# PG04_Schematic_Sheet2.net
KiCad netlist of a schematic drawn in Altium Designer
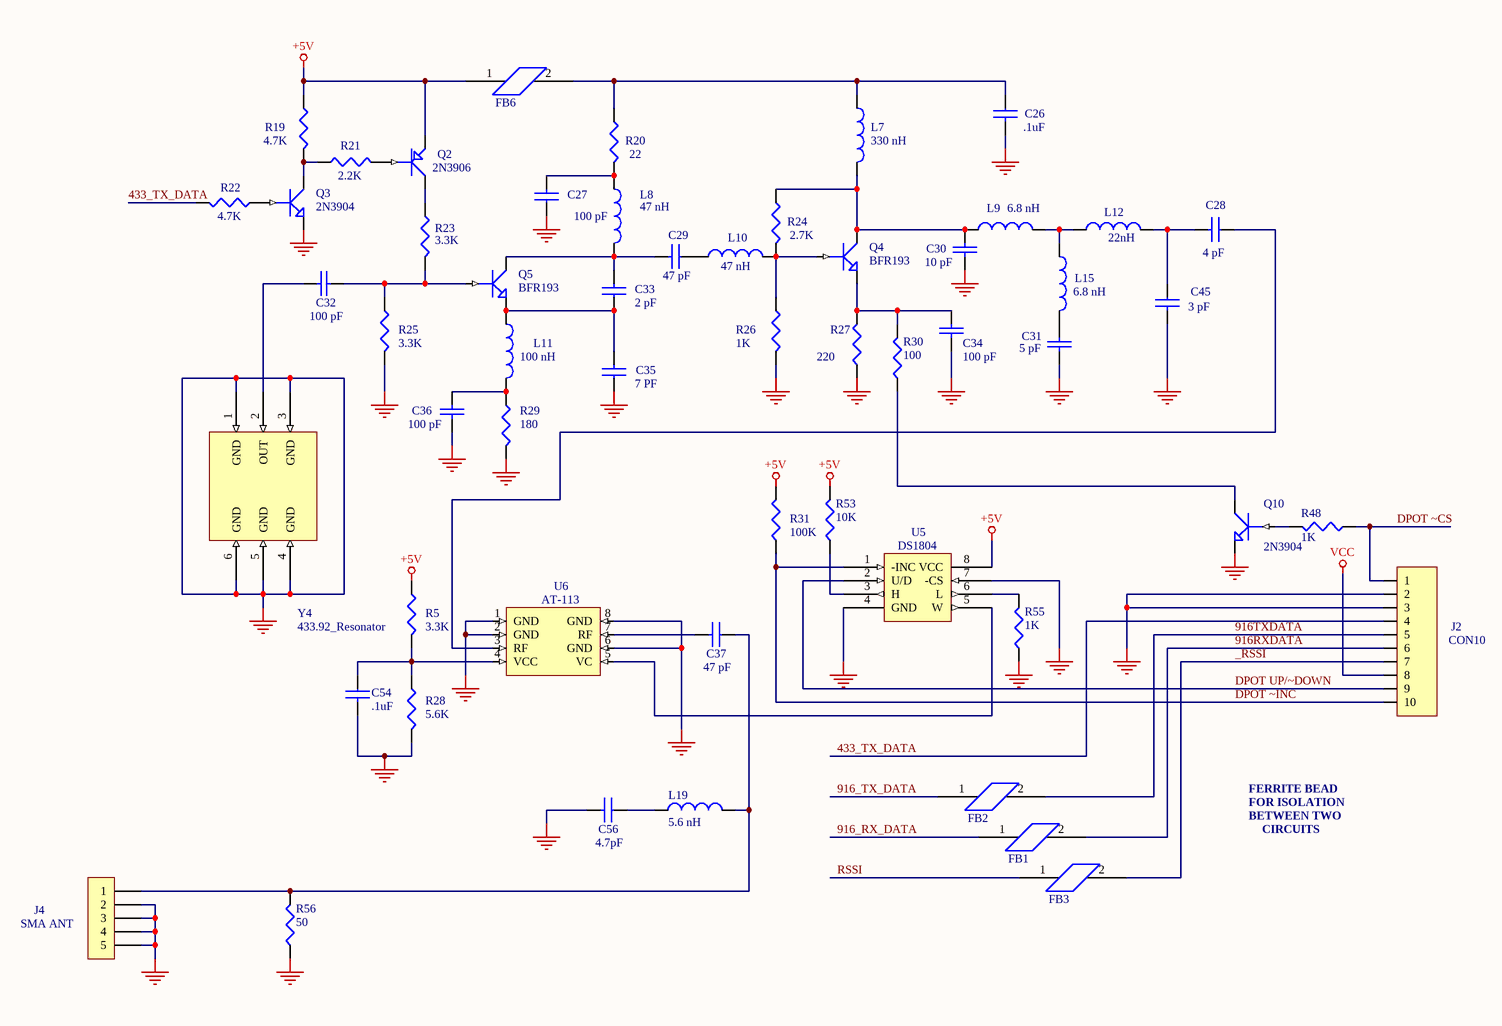
[diagram p0: PG04_Schematic Sheet2.SchDoc]

(export (version "E")
  (design (tool "Eeschema 10.0.6"))
  (components
    (comp (ref "C26") (value ".1uF") (footprint "0603") (libsource (lib "*") (part "CAP_NP")))
    (comp (ref "C27") (value "100 pF") (footprint "0603") (libsource (lib "*") (part "CAP_NP")))
    (comp (ref "C28") (value "4 pF") (footprint "0603") (libsource (lib "*") (part "CAP_NP")))
    (comp (ref "C29") (value "47 pF") (footprint "0603") (libsource (lib "*") (part "CAP_NP")))
    (comp (ref "C30")
      (value "10 pF")
      (footprint "0603")
      (description "Capacitor")
      (libsource (lib "*") (part "CAP"))
    )
    (comp (ref "C31")
      (value "5 pF")
      (footprint "0603")
      (description "Capacitor")
      (libsource (lib "*") (part "CAP"))
    )
    (comp (ref "C32")
      (value "100 pF")
      (footprint "0603")
      (description "Capacitor")
      (libsource (lib "*") (part "CAP"))
    )
    (comp (ref "C33") (value "2 pF") (footprint "0603") (libsource (lib "*") (part "CAP_NP")))
    (comp (ref "C34")
      (value "100 pF")
      (footprint "0603")
      (description "Capacitor")
      (libsource (lib "*") (part "CAP"))
    )
    (comp (ref "C35") (value "7 PF") (footprint "0603") (libsource (lib "*") (part "CAP_NP")))
    (comp (ref "C36")
      (value "100 pF")
      (footprint "0603")
      (description "Capacitor")
      (libsource (lib "*") (part "CAP"))
    )
    (comp (ref "C37") (value "47 pF") (footprint "0603") (libsource (lib "*") (part "CAP_NP")))
    (comp (ref "C45") (value "3 pF") (footprint "0603") (libsource (lib "*") (part "CAP_NP")))
    (comp (ref "C54") (value ".1uF") (footprint "0603") (libsource (lib "*") (part "CAP_NP")))
    (comp (ref "C56") (value "4.7pF") (footprint "0603") (libsource (lib "*") (part "CAP_NP")))
    (comp (ref "FB1") (value "FB") (footprint "0603") (libsource (lib "*") (part "FB_0603")))
    (comp (ref "FB2") (value "FB") (footprint "0603") (libsource (lib "*") (part "FB_0603")))
    (comp (ref "FB3") (value "FB") (footprint "0603") (libsource (lib "*") (part "FB_0603")))
    (comp (ref "FB6") (value "FB") (footprint "0603") (libsource (lib "*") (part "FB_0603")))
    (comp (ref "J2") (value "CON10") (footprint "1X10 HEADER") (libsource (lib "*") (part "CON10")))
    (comp (ref "J4")
      (value "SMA ANT")
      (footprint "50 OHM ANT")
      (description "Connector")
      (libsource (lib "*") (part "CON5"))
    )
    (comp (ref "L7") (value "330 nH") (footprint "0805") (libsource (lib "*") (part "INDUCTOR")))
    (comp (ref "L8") (value "47 nH") (footprint "0603") (libsource (lib "*") (part "INDUCTOR")))
    (comp (ref "L9") (value "6.8 nH") (footprint "0603") (libsource (lib "*") (part "INDUCTOR")))
    (comp (ref "L10") (value "47 nH") (footprint "0603") (libsource (lib "*") (part "INDUCTOR")))
    (comp (ref "L11") (value "100 nH") (footprint "0603") (libsource (lib "*") (part "INDUCTOR")))
    (comp (ref "L12") (value "22nH") (footprint "0603") (libsource (lib "*") (part "INDUCTOR")))
    (comp (ref "L15") (value "6.8 nH") (footprint "0603") (libsource (lib "*") (part "INDUCTOR")))
    (comp (ref "L19") (value "5.6 nH") (footprint "0603") (libsource (lib "*") (part "INDUCTOR")))
    (comp (ref "Q2")
      (value "2N3906")
      (footprint "SOT23 TRANS")
      (description "PNP Transistor")
      (libsource (lib "*") (part "PNP1"))
    )
    (comp (ref "Q3")
      (value "2N3904")
      (footprint "SOT23 TRANS")
      (description "NPN Transistor")
      (libsource (lib "*") (part "NPN1"))
    )
    (comp (ref "Q4")
      (value "BFR193")
      (footprint "SOT23 TRANS")
      (description "NPN Transistor")
      (libsource (lib "*") (part "NPN1"))
    )
    (comp (ref "Q5")
      (value "BFR193")
      (footprint "SOT23 TRANS")
      (description "NPN Transistor")
      (libsource (lib "*") (part "NPN1"))
    )
    (comp (ref "Q10")
      (value "2N3904")
      (footprint "SOT23 TRANS")
      (description "NPN Transistor")
      (libsource (lib "*") (part "NPN1"))
    )
    (comp (ref "R5") (value "3.3K") (footprint "0603") (libsource (lib "*") (part "RESISTOR")))
    (comp (ref "R19") (value "4.7K") (footprint "0603") (libsource (lib "*") (part "RESISTOR")))
    (comp (ref "R20") (value "22") (footprint "0603") (libsource (lib "*") (part "RESISTOR")))
    (comp (ref "R21") (value "2.2K") (footprint "0603") (libsource (lib "*") (part "RESISTOR")))
    (comp (ref "R22") (value "4.7K") (footprint "0603") (libsource (lib "*") (part "RESISTOR")))
    (comp (ref "R23") (value "3.3K") (footprint "0603") (libsource (lib "*") (part "RESISTOR")))
    (comp (ref "R24") (value "2.7K") (footprint "0603") (libsource (lib "*") (part "RESISTOR")))
    (comp (ref "R25") (value "3.3K") (footprint "0603") (libsource (lib "*") (part "RESISTOR")))
    (comp (ref "R26") (value "1K") (footprint "0603") (libsource (lib "*") (part "RESISTOR")))
    (comp (ref "R27") (value "220") (footprint "0603") (libsource (lib "*") (part "RESISTOR")))
    (comp (ref "R28") (value "5.6K") (footprint "0603") (libsource (lib "*") (part "RESISTOR")))
    (comp (ref "R29") (value "180") (footprint "0603") (libsource (lib "*") (part "RESISTOR")))
    (comp (ref "R30") (value "100") (footprint "0603") (libsource (lib "*") (part "RESISTOR")))
    (comp (ref "R31") (value "100K") (footprint "0603") (libsource (lib "*") (part "RESISTOR")))
    (comp (ref "R48") (value "1K") (footprint "0603") (libsource (lib "*") (part "RESISTOR")))
    (comp (ref "R53") (value "10K") (footprint "0603") (libsource (lib "*") (part "RESISTOR")))
    (comp (ref "R55") (value "1K") (footprint "0603") (libsource (lib "*") (part "RESISTOR")))
    (comp (ref "R56") (value "50") (footprint "0603") (libsource (lib "*") (part "RESISTOR")))
    (comp (ref "U5") (value "DS1804") (footprint "SO8 SMALL") (libsource (lib "*") (part "DS1804")))
    (comp (ref "U6") (value "AT-113") (footprint "SO8") (libsource (lib "*") (part "AT-113A")))
    (comp (ref "Y4")
      (value "433.92_Resonator")
      (footprint "RESONATOR2")
      (libsource (lib "*") (part "RESONATOR2"))
    )
  )
  (nets
    (net (code "1") (name "+5V") (class "Default")
      (node (ref "FB6") (pin "1") (pinfunction "2_1") (pintype "passive"))
      (node (ref "Q2") (pin "E") (pinfunction "E_E") (pintype "passive"))
      (node (ref "R19") (pin "1") (pinfunction "1_1") (pintype "passive"))
      (node (ref "R31") (pin "1") (pinfunction "1_1") (pintype "passive"))
      (node (ref "R5") (pin "1") (pinfunction "1_1") (pintype "passive"))
      (node (ref "R53") (pin "2") (pinfunction "2_2") (pintype "passive"))
      (node (ref "U5") (pin "8") (pinfunction "VCC_8") (pintype "power_in"))
    )
    (net (code "2") (name "/433_TX_DATA") (class "Default")
      (node (ref "J2") (pin "4") (pinfunction "4_4") (pintype "passive"))
      (node (ref "R22") (pin "2") (pinfunction "2_2") (pintype "passive"))
    )
    (net (code "3") (name "/916RXDATA") (class "Default")
      (node (ref "FB1") (pin "2") (pinfunction "1_2") (pintype "passive"))
      (node (ref "J2") (pin "6") (pinfunction "6_6") (pintype "passive"))
    )
    (net (code "4") (name "/916TXDATA") (class "Default")
      (node (ref "FB2") (pin "2") (pinfunction "1_2") (pintype "passive"))
      (node (ref "J2") (pin "5") (pinfunction "5_5") (pintype "passive"))
    )
    (net (code "5") (name "/916_RX_DATA") (class "Default")
      (node (ref "FB1") (pin "1") (pinfunction "2_1") (pintype "passive"))
    )
    (net (code "6") (name "/916_TX_DATA") (class "Default")
      (node (ref "FB2") (pin "1") (pinfunction "2_1") (pintype "passive"))
    )
    (net (code "7") (name "/DPOT UP{slash}~DOWN") (class "Default")
      (node (ref "J2") (pin "9") (pinfunction "9_9") (pintype "passive"))
      (node (ref "U5") (pin "2") (pinfunction "U/D_2") (pintype "input"))
    )
    (net (code "8") (name "/DPOT ~CS") (class "Default")
      (node (ref "J2") (pin "1") (pinfunction "1_1") (pintype "passive"))
      (node (ref "R48") (pin "2") (pinfunction "2_2") (pintype "passive"))
    )
    (net (code "9") (name "/DPOT ~INC") (class "Default")
      (node (ref "J2") (pin "10") (pinfunction "10_10") (pintype "passive"))
      (node (ref "R31") (pin "2") (pinfunction "2_2") (pintype "passive"))
      (node (ref "U5") (pin "1") (pinfunction "-INC_1") (pintype "input"))
    )
    (net (code "10") (name "/RSSI") (class "Default")
      (node (ref "FB3") (pin "1") (pinfunction "2_1") (pintype "passive"))
    )
    (net (code "11") (name "/_RSSI") (class "Default")
      (node (ref "FB3") (pin "2") (pinfunction "1_2") (pintype "passive"))
      (node (ref "J2") (pin "7") (pinfunction "7_7") (pintype "passive"))
    )
    (net (code "12") (name "GND_SIGNAL") (class "Default")
      (node (ref "C26") (pin "2") (pinfunction "2_2") (pintype "passive"))
      (node (ref "C27") (pin "1") (pinfunction "1_1") (pintype "passive"))
      (node (ref "C30") (pin "2") (pinfunction "2_2") (pintype "passive"))
      (node (ref "C31") (pin "2") (pinfunction "2_2") (pintype "passive"))
      (node (ref "C34") (pin "2") (pinfunction "2_2") (pintype "passive"))
      (node (ref "C35") (pin "1") (pinfunction "1_1") (pintype "passive"))
      (node (ref "C36") (pin "2") (pinfunction "2_2") (pintype "passive"))
      (node (ref "C45") (pin "2") (pinfunction "2_2") (pintype "passive"))
      (node (ref "C54") (pin "2") (pinfunction "2_2") (pintype "passive"))
      (node (ref "C56") (pin "2") (pinfunction "2_2") (pintype "passive"))
      (node (ref "J2") (pin "2") (pinfunction "2_2") (pintype "passive"))
      (node (ref "J2") (pin "3") (pinfunction "3_3") (pintype "passive"))
      (node (ref "J4") (pin "2") (pinfunction "2_2") (pintype "passive"))
      (node (ref "J4") (pin "3") (pinfunction "3_3") (pintype "passive"))
      (node (ref "J4") (pin "4") (pinfunction "4_4") (pintype "passive"))
      (node (ref "J4") (pin "5") (pinfunction "5_5") (pintype "passive"))
      (node (ref "Q10") (pin "E") (pinfunction "E_E") (pintype "passive"))
      (node (ref "Q3") (pin "E") (pinfunction "E_E") (pintype "passive"))
      (node (ref "R25") (pin "2") (pinfunction "2_2") (pintype "passive"))
      (node (ref "R26") (pin "2") (pinfunction "2_2") (pintype "passive"))
      (node (ref "R27") (pin "2") (pinfunction "2_2") (pintype "passive"))
      (node (ref "R28") (pin "2") (pinfunction "2_2") (pintype "passive"))
      (node (ref "R29") (pin "2") (pinfunction "2_2") (pintype "passive"))
      (node (ref "R55") (pin "1") (pinfunction "1_1") (pintype "passive"))
      (node (ref "R56") (pin "1") (pinfunction "1_1") (pintype "passive"))
      (node (ref "U5") (pin "4") (pinfunction "GND_4") (pintype "power_in"))
      (node (ref "U5") (pin "7") (pinfunction "-CS_7") (pintype "input"))
      (node (ref "U6") (pin "1") (pinfunction "GND_1") (pintype "input"))
      (node (ref "U6") (pin "2") (pinfunction "GND_2") (pintype "input"))
      (node (ref "U6") (pin "6") (pinfunction "GND_6") (pintype "input"))
      (node (ref "U6") (pin "8") (pinfunction "GND_8") (pintype "input"))
      (node (ref "Y4") (pin "1") (pinfunction "GND_1") (pintype "input"))
      (node (ref "Y4") (pin "3") (pinfunction "GND_3") (pintype "input"))
      (node (ref "Y4") (pin "4") (pinfunction "GND_4") (pintype "input"))
      (node (ref "Y4") (pin "5") (pinfunction "GND_5") (pintype "input"))
      (node (ref "Y4") (pin "6") (pinfunction "GND_6") (pintype "input"))
    )
    (net (code "13") (name "Net-(C27-Pad2)") (class "Default")
      (node (ref "C27") (pin "2") (pinfunction "2_2") (pintype "passive"))
      (node (ref "L8") (pin "1") (pinfunction "1_1") (pintype "passive"))
      (node (ref "R20") (pin "2") (pinfunction "2_2") (pintype "passive"))
    )
    (net (code "14") (name "Net-(C28-Pad1)") (class "Default")
      (node (ref "C28") (pin "1") (pinfunction "1_1") (pintype "passive"))
      (node (ref "U6") (pin "3") (pinfunction "RF_3") (pintype "input"))
    )
    (net (code "15") (name "Net-(C28-Pad2)") (class "Default")
      (node (ref "C28") (pin "2") (pinfunction "2_2") (pintype "passive"))
      (node (ref "C45") (pin "1") (pinfunction "1_1") (pintype "passive"))
      (node (ref "L12") (pin "2") (pinfunction "2_2") (pintype "passive"))
    )
    (net (code "16") (name "Net-(C29-Pad1)") (class "Default")
      (node (ref "C29") (pin "1") (pinfunction "1_1") (pintype "passive"))
      (node (ref "L10") (pin "1") (pinfunction "1_1") (pintype "passive"))
    )
    (net (code "17") (name "Net-(C29-Pad2)") (class "Default")
      (node (ref "C29") (pin "2") (pinfunction "2_2") (pintype "passive"))
      (node (ref "C33") (pin "2") (pinfunction "2_2") (pintype "passive"))
      (node (ref "L8") (pin "2") (pinfunction "2_2") (pintype "passive"))
      (node (ref "Q5") (pin "C") (pinfunction "C_C") (pintype "passive"))
    )
    (net (code "18") (name "Net-(C30-Pad1)") (class "Default")
      (node (ref "C30") (pin "1") (pinfunction "1_1") (pintype "passive"))
      (node (ref "L7") (pin "2") (pinfunction "2_2") (pintype "passive"))
      (node (ref "L9") (pin "1") (pinfunction "1_1") (pintype "passive"))
      (node (ref "Q4") (pin "C") (pinfunction "C_C") (pintype "passive"))
      (node (ref "R24") (pin "1") (pinfunction "1_1") (pintype "passive"))
    )
    (net (code "19") (name "Net-(C31-Pad1)") (class "Default")
      (node (ref "C31") (pin "1") (pinfunction "1_1") (pintype "passive"))
      (node (ref "L15") (pin "2") (pinfunction "2_2") (pintype "passive"))
    )
    (net (code "20") (name "Net-(C32-Pad2)") (class "Default")
      (node (ref "C32") (pin "2") (pinfunction "2_2") (pintype "passive"))
      (node (ref "Q5") (pin "B") (pinfunction "B_B") (pintype "input"))
      (node (ref "R23") (pin "2") (pinfunction "2_2") (pintype "passive"))
      (node (ref "R25") (pin "1") (pinfunction "1_1") (pintype "passive"))
    )
    (net (code "21") (name "Net-(C33-Pad1)") (class "Default")
      (node (ref "C33") (pin "1") (pinfunction "1_1") (pintype "passive"))
      (node (ref "C35") (pin "2") (pinfunction "2_2") (pintype "passive"))
      (node (ref "L11") (pin "1") (pinfunction "1_1") (pintype "passive"))
      (node (ref "Q5") (pin "E") (pinfunction "E_E") (pintype "passive"))
    )
    (net (code "22") (name "Net-(C34-Pad1)") (class "Default")
      (node (ref "C34") (pin "1") (pinfunction "1_1") (pintype "passive"))
      (node (ref "Q4") (pin "E") (pinfunction "E_E") (pintype "passive"))
      (node (ref "R27") (pin "1") (pinfunction "1_1") (pintype "passive"))
      (node (ref "R30") (pin "2") (pinfunction "2_2") (pintype "passive"))
    )
    (net (code "23") (name "Net-(C36-Pad1)") (class "Default")
      (node (ref "C36") (pin "1") (pinfunction "1_1") (pintype "passive"))
      (node (ref "L11") (pin "2") (pinfunction "2_2") (pintype "passive"))
      (node (ref "R29") (pin "1") (pinfunction "1_1") (pintype "passive"))
    )
    (net (code "24") (name "Net-(C37-Pad1)") (class "Default")
      (node (ref "C37") (pin "1") (pinfunction "1_1") (pintype "passive"))
      (node (ref "J4") (pin "1") (pinfunction "1_1") (pintype "passive"))
      (node (ref "L19") (pin "2") (pinfunction "2_2") (pintype "passive"))
      (node (ref "R56") (pin "2") (pinfunction "2_2") (pintype "passive"))
    )
    (net (code "25") (name "Net-(C37-Pad2)") (class "Default")
      (node (ref "C37") (pin "2") (pinfunction "2_2") (pintype "passive"))
      (node (ref "U6") (pin "7") (pinfunction "RF_7") (pintype "input"))
    )
    (net (code "26") (name "Net-(C56-Pad1)") (class "Default")
      (node (ref "C56") (pin "1") (pinfunction "1_1") (pintype "passive"))
      (node (ref "L19") (pin "1") (pinfunction "1_1") (pintype "passive"))
    )
    (net (code "27") (name "Net-(FB6-1)") (class "Default")
      (node (ref "C26") (pin "1") (pinfunction "1_1") (pintype "passive"))
      (node (ref "FB6") (pin "2") (pinfunction "1_2") (pintype "passive"))
      (node (ref "L7") (pin "1") (pinfunction "1_1") (pintype "passive"))
      (node (ref "R20") (pin "1") (pinfunction "1_1") (pintype "passive"))
    )
    (net (code "28") (name "Net-(L10-Pad2)") (class "Default")
      (node (ref "L10") (pin "2") (pinfunction "2_2") (pintype "passive"))
      (node (ref "Q4") (pin "B") (pinfunction "B_B") (pintype "input"))
      (node (ref "R24") (pin "2") (pinfunction "2_2") (pintype "passive"))
      (node (ref "R26") (pin "1") (pinfunction "1_1") (pintype "passive"))
    )
    (net (code "29") (name "Net-(L12-Pad1)") (class "Default")
      (node (ref "L12") (pin "1") (pinfunction "1_1") (pintype "passive"))
      (node (ref "L15") (pin "1") (pinfunction "1_1") (pintype "passive"))
      (node (ref "L9") (pin "2") (pinfunction "2_2") (pintype "passive"))
    )
    (net (code "30") (name "Net-(Q2-PadB)") (class "Default")
      (node (ref "Q2") (pin "B") (pinfunction "B_B") (pintype "input"))
      (node (ref "R21") (pin "2") (pinfunction "2_2") (pintype "passive"))
    )
    (net (code "31") (name "Net-(Q2-PadC)") (class "Default")
      (node (ref "Q2") (pin "C") (pinfunction "C_C") (pintype "passive"))
      (node (ref "R23") (pin "1") (pinfunction "1_1") (pintype "passive"))
    )
    (net (code "32") (name "Net-(Q3-PadB)") (class "Default")
      (node (ref "Q3") (pin "B") (pinfunction "B_B") (pintype "input"))
      (node (ref "R22") (pin "1") (pinfunction "1_1") (pintype "passive"))
    )
    (net (code "33") (name "Net-(Q3-PadC)") (class "Default")
      (node (ref "Q3") (pin "C") (pinfunction "C_C") (pintype "passive"))
      (node (ref "R19") (pin "2") (pinfunction "2_2") (pintype "passive"))
      (node (ref "R21") (pin "1") (pinfunction "1_1") (pintype "passive"))
    )
    (net (code "34") (name "Net-(Q10-PadB)") (class "Default")
      (node (ref "Q10") (pin "B") (pinfunction "B_B") (pintype "input"))
      (node (ref "R48") (pin "1") (pinfunction "1_1") (pintype "passive"))
    )
    (net (code "35") (name "Net-(Q10-PadC)") (class "Default")
      (node (ref "Q10") (pin "C") (pinfunction "C_C") (pintype "passive"))
      (node (ref "R30") (pin "1") (pinfunction "1_1") (pintype "passive"))
    )
    (net (code "36") (name "Net-(U5-H)") (class "Default")
      (node (ref "R53") (pin "1") (pinfunction "1_1") (pintype "passive"))
      (node (ref "U5") (pin "3") (pinfunction "H_3") (pintype "output"))
    )
    (net (code "37") (name "Net-(U5-L)") (class "Default")
      (node (ref "R55") (pin "2") (pinfunction "2_2") (pintype "passive"))
      (node (ref "U5") (pin "6") (pinfunction "L_6") (pintype "output"))
    )
    (net (code "38") (name "Net-(U5-W)") (class "Default")
      (node (ref "U5") (pin "5") (pinfunction "W_5") (pintype "output"))
      (node (ref "U6") (pin "5") (pinfunction "VC_5") (pintype "input"))
    )
    (net (code "39") (name "Net-(U6-VCC)") (class "Default")
      (node (ref "C54") (pin "1") (pinfunction "1_1") (pintype "passive"))
      (node (ref "R28") (pin "1") (pinfunction "1_1") (pintype "passive"))
      (node (ref "R5") (pin "2") (pinfunction "2_2") (pintype "passive"))
      (node (ref "U6") (pin "4") (pinfunction "VCC_4") (pintype "input"))
    )
    (net (code "40") (name "Net-(Y4-OUT)") (class "Default")
      (node (ref "C32") (pin "1") (pinfunction "1_1") (pintype "passive"))
      (node (ref "Y4") (pin "2") (pinfunction "OUT_2") (pintype "input"))
    )
    (net (code "41") (name "VCC") (class "Default")
      (node (ref "J2") (pin "8") (pinfunction "8_8") (pintype "passive"))
    )
  )
)
